# 301_GridPos3.net
KiCad netlist of a schematic drawn in Altium Designer
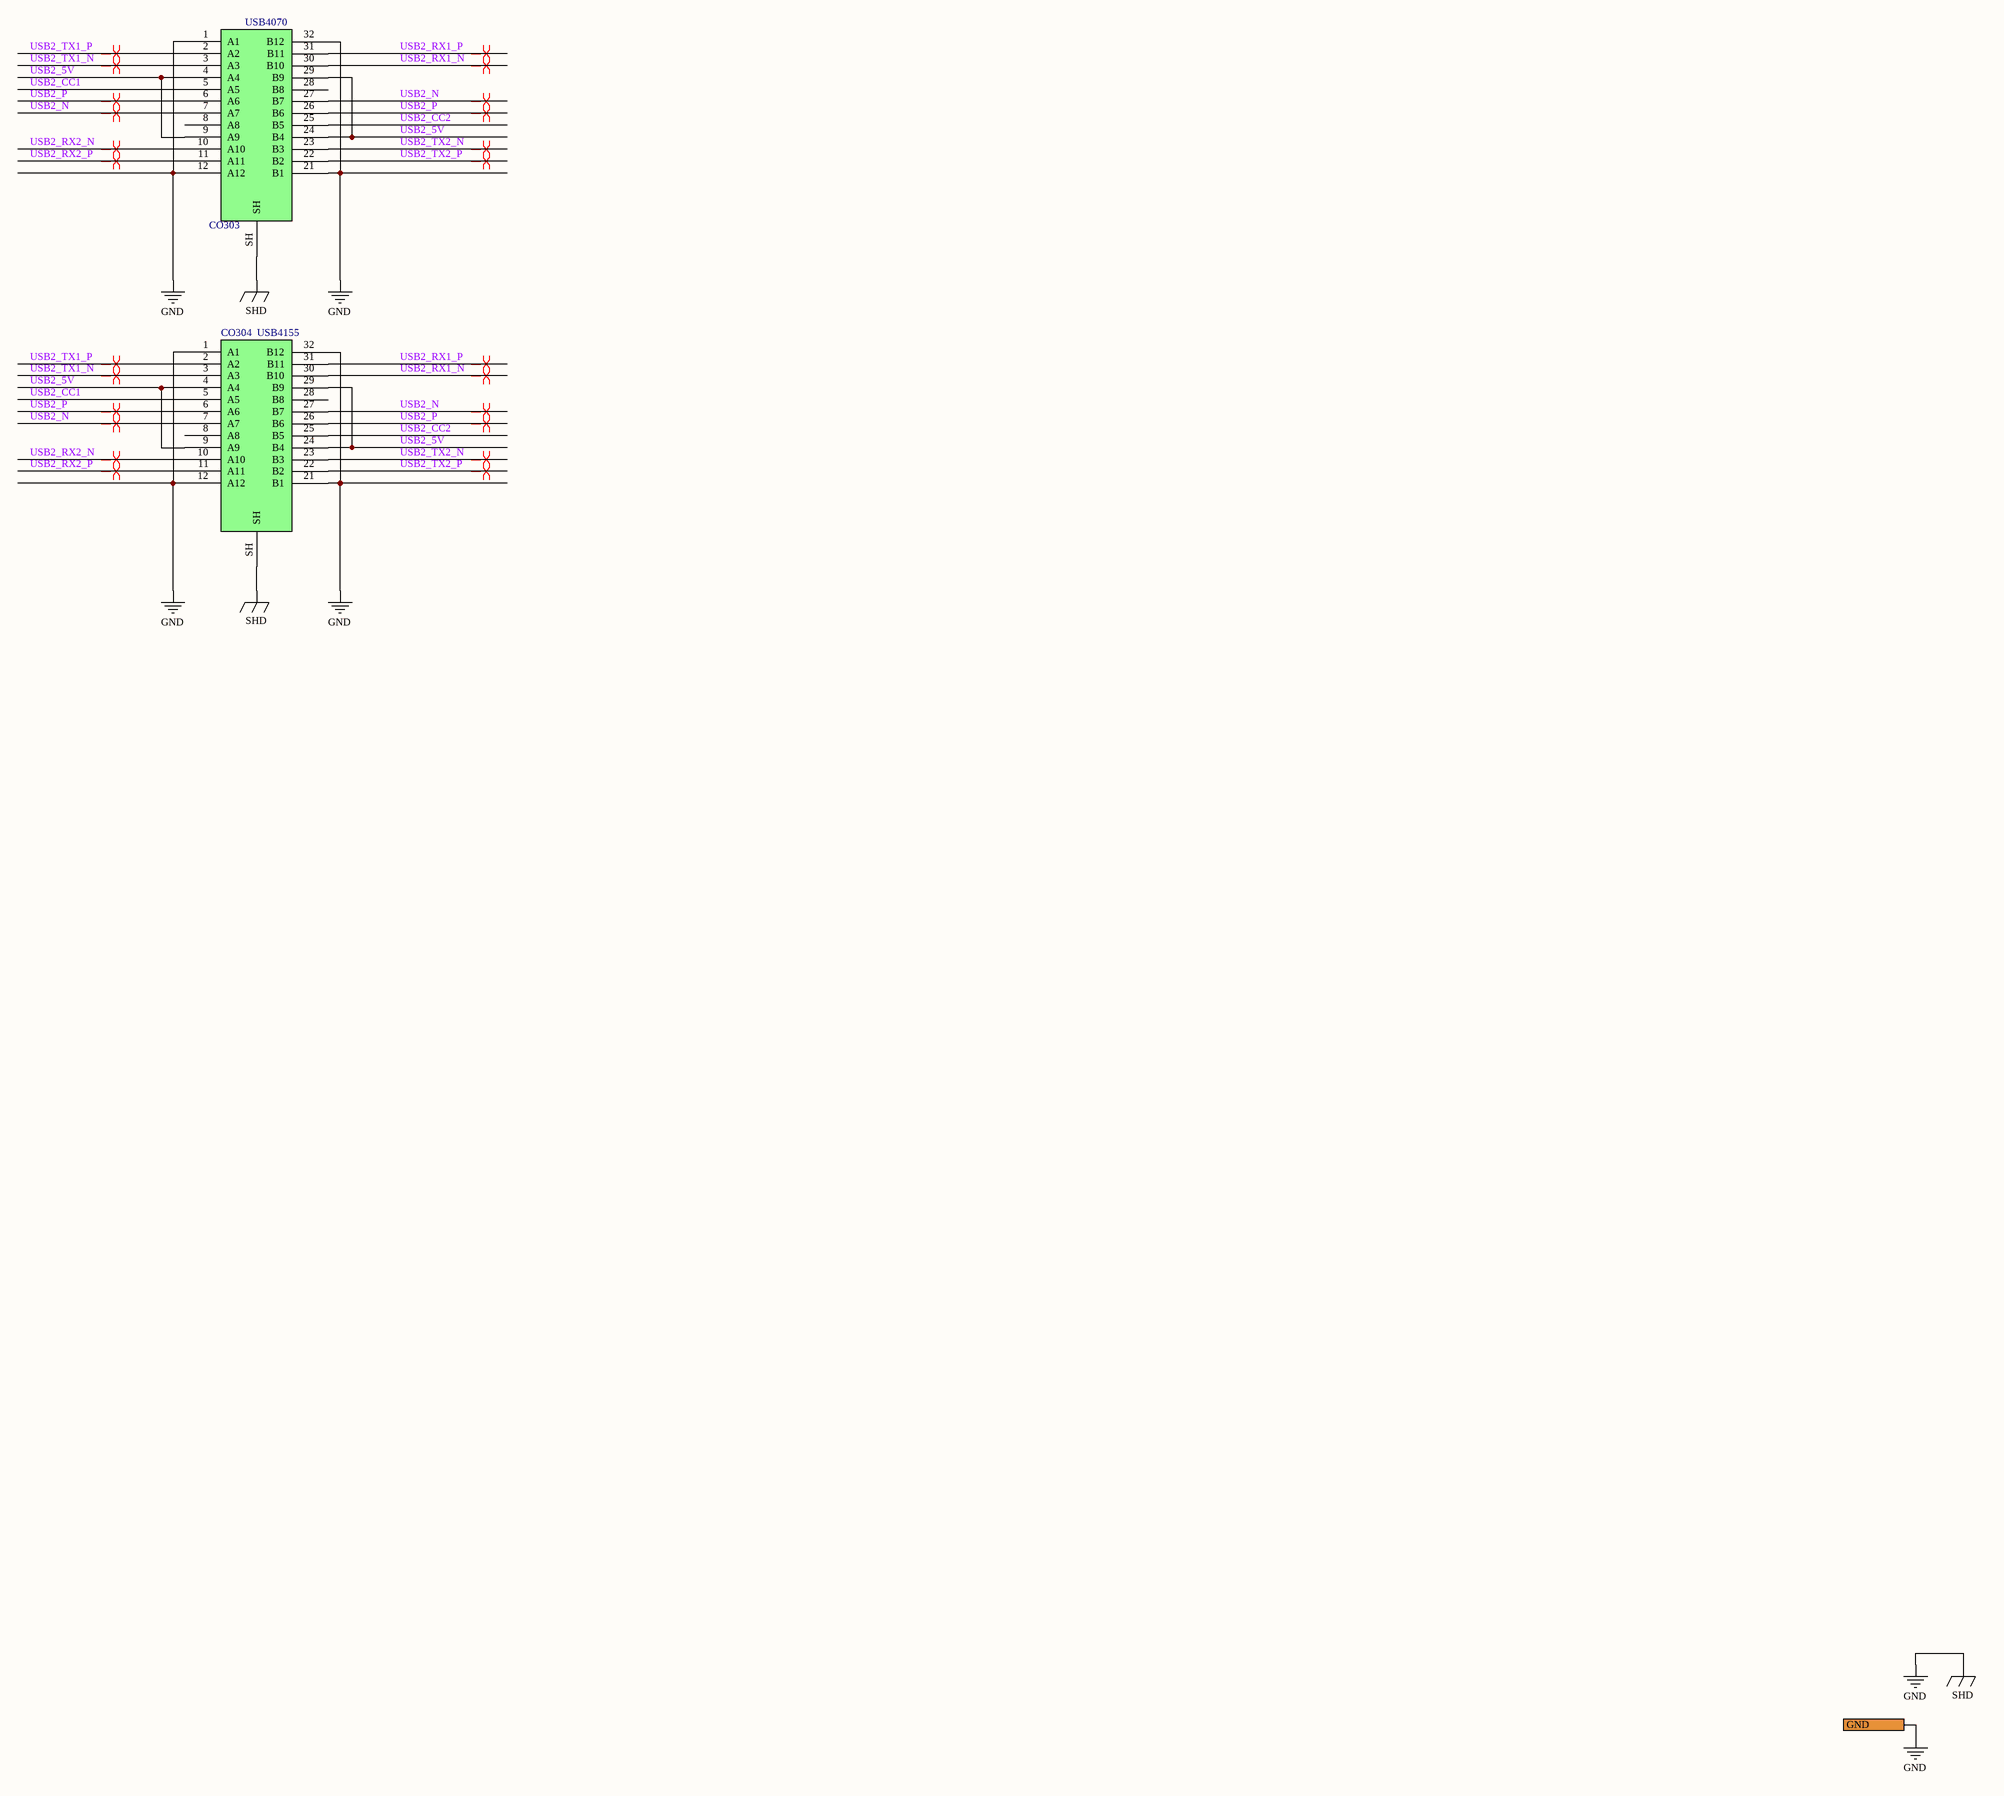
[diagram p0: 301_GridPos3.SchDoc]

(export (version "E")
  (design (tool "Eeschema 10.0.6"))
  (components
    (comp (ref "CO303")
      (value "USB4070")
      (footprint "USB4070-30-C")
      (description "USB C connector Receptacle Vertical")
      (fields
        (field (name "REFVAL") "USB4070")
        (field (name "PART NUMBER") "CO0021")
        (field (name "MANFACTPART") "USB4070-30-C")
      )
      (libsource (lib "GTS_Database") (part "USB-CC"))
    )
    (comp (ref "CO304")
      (value "USB4155")
      (footprint "USB4155-03-C")
      (description "USB C connector Plug Horizontal")
      (fields
        (field (name "REFVAL") "USB4155")
        (field (name "PART NUMBER") "CO0031")
        (field (name "MANFACTPART") "USB4155-03-C")
      )
      (libsource (lib "GTS_Database") (part "USB-CC"))
    )
  )
  (nets
    (net (code "1") (name "/USB2_5V") (class "Default")
      (node (ref "CO303") (pin "24") (pinfunction "B4_24") (pintype "passive"))
      (node (ref "CO303") (pin "29") (pinfunction "B9_29") (pintype "passive"))
      (node (ref "CO303") (pin "4") (pinfunction "A4_4") (pintype "passive"))
      (node (ref "CO303") (pin "9") (pinfunction "A9_9") (pintype "passive"))
      (node (ref "CO304") (pin "24") (pinfunction "B4_24") (pintype "passive"))
      (node (ref "CO304") (pin "29") (pinfunction "B9_29") (pintype "passive"))
      (node (ref "CO304") (pin "4") (pinfunction "A4_4") (pintype "passive"))
      (node (ref "CO304") (pin "9") (pinfunction "A9_9") (pintype "passive"))
    )
    (net (code "2") (name "/USB2_CC1") (class "Default")
      (node (ref "CO303") (pin "5") (pinfunction "A5_5") (pintype "passive"))
      (node (ref "CO304") (pin "5") (pinfunction "A5_5") (pintype "passive"))
    )
    (net (code "3") (name "/USB2_CC2") (class "Default")
      (node (ref "CO303") (pin "25") (pinfunction "B5_25") (pintype "passive"))
      (node (ref "CO304") (pin "25") (pinfunction "B5_25") (pintype "passive"))
    )
    (net (code "4") (name "/USB2_N") (class "Default")
      (node (ref "CO303") (pin "27") (pinfunction "B7_27") (pintype "passive"))
      (node (ref "CO303") (pin "7") (pinfunction "A7_7") (pintype "passive"))
      (node (ref "CO304") (pin "27") (pinfunction "B7_27") (pintype "passive"))
      (node (ref "CO304") (pin "7") (pinfunction "A7_7") (pintype "passive"))
    )
    (net (code "5") (name "/USB2_P") (class "Default")
      (node (ref "CO303") (pin "26") (pinfunction "B6_26") (pintype "passive"))
      (node (ref "CO303") (pin "6") (pinfunction "A6_6") (pintype "passive"))
      (node (ref "CO304") (pin "26") (pinfunction "B6_26") (pintype "passive"))
      (node (ref "CO304") (pin "6") (pinfunction "A6_6") (pintype "passive"))
    )
    (net (code "6") (name "/USB2_RX1_N") (class "Default")
      (node (ref "CO303") (pin "30") (pinfunction "B10_30") (pintype "passive"))
      (node (ref "CO304") (pin "30") (pinfunction "B10_30") (pintype "passive"))
    )
    (net (code "7") (name "/USB2_RX1_P") (class "Default")
      (node (ref "CO303") (pin "31") (pinfunction "B11_31") (pintype "passive"))
      (node (ref "CO304") (pin "31") (pinfunction "B11_31") (pintype "passive"))
    )
    (net (code "8") (name "/USB2_RX2_N") (class "Default")
      (node (ref "CO303") (pin "10") (pinfunction "A10_10") (pintype "passive"))
      (node (ref "CO304") (pin "10") (pinfunction "A10_10") (pintype "passive"))
    )
    (net (code "9") (name "/USB2_RX2_P") (class "Default")
      (node (ref "CO303") (pin "11") (pinfunction "A11_11") (pintype "passive"))
      (node (ref "CO304") (pin "11") (pinfunction "A11_11") (pintype "passive"))
    )
    (net (code "10") (name "/USB2_TX1_N") (class "Default")
      (node (ref "CO303") (pin "3") (pinfunction "A3_3") (pintype "passive"))
      (node (ref "CO304") (pin "3") (pinfunction "A3_3") (pintype "passive"))
    )
    (net (code "11") (name "/USB2_TX1_P") (class "Default")
      (node (ref "CO303") (pin "2") (pinfunction "A2_2") (pintype "passive"))
      (node (ref "CO304") (pin "2") (pinfunction "A2_2") (pintype "passive"))
    )
    (net (code "12") (name "/USB2_TX2_N") (class "Default")
      (node (ref "CO303") (pin "23") (pinfunction "B3_23") (pintype "passive"))
      (node (ref "CO304") (pin "23") (pinfunction "B3_23") (pintype "passive"))
    )
    (net (code "13") (name "/USB2_TX2_P") (class "Default")
      (node (ref "CO303") (pin "22") (pinfunction "B2_22") (pintype "passive"))
      (node (ref "CO304") (pin "22") (pinfunction "B2_22") (pintype "passive"))
    )
    (net (code "14") (name "GND") (class "Default")
      (node (ref "CO303") (pin "1") (pinfunction "A1_1") (pintype "passive"))
      (node (ref "CO303") (pin "12") (pinfunction "A12_12") (pintype "passive"))
      (node (ref "CO303") (pin "21") (pinfunction "B1_21") (pintype "passive"))
      (node (ref "CO303") (pin "32") (pinfunction "B12_32") (pintype "passive"))
      (node (ref "CO303") (pin "SH") (pinfunction "SH_SH") (pintype "power_in"))
      (node (ref "CO304") (pin "1") (pinfunction "A1_1") (pintype "passive"))
      (node (ref "CO304") (pin "12") (pinfunction "A12_12") (pintype "passive"))
      (node (ref "CO304") (pin "21") (pinfunction "B1_21") (pintype "passive"))
      (node (ref "CO304") (pin "32") (pinfunction "B12_32") (pintype "passive"))
      (node (ref "CO304") (pin "SH") (pinfunction "SH_SH") (pintype "power_in"))
    )
    (net (code "15") (name "unconnected-(CO303-A8-Pad8)") (class "Default")
      (node (ref "CO303") (pin "8") (pinfunction "A8_8") (pintype "passive"))
    )
    (net (code "16") (name "unconnected-(CO303-B8-Pad28)") (class "Default")
      (node (ref "CO303") (pin "28") (pinfunction "B8_28") (pintype "passive"))
    )
    (net (code "17") (name "unconnected-(CO304-A8-Pad8)") (class "Default")
      (node (ref "CO304") (pin "8") (pinfunction "A8_8") (pintype "passive"))
    )
    (net (code "18") (name "unconnected-(CO304-B8-Pad28)") (class "Default")
      (node (ref "CO304") (pin "28") (pinfunction "B8_28") (pintype "passive"))
    )
  )
)
